# yin_bit.net
KiCad netlist of a schematic drawn in EAGLE
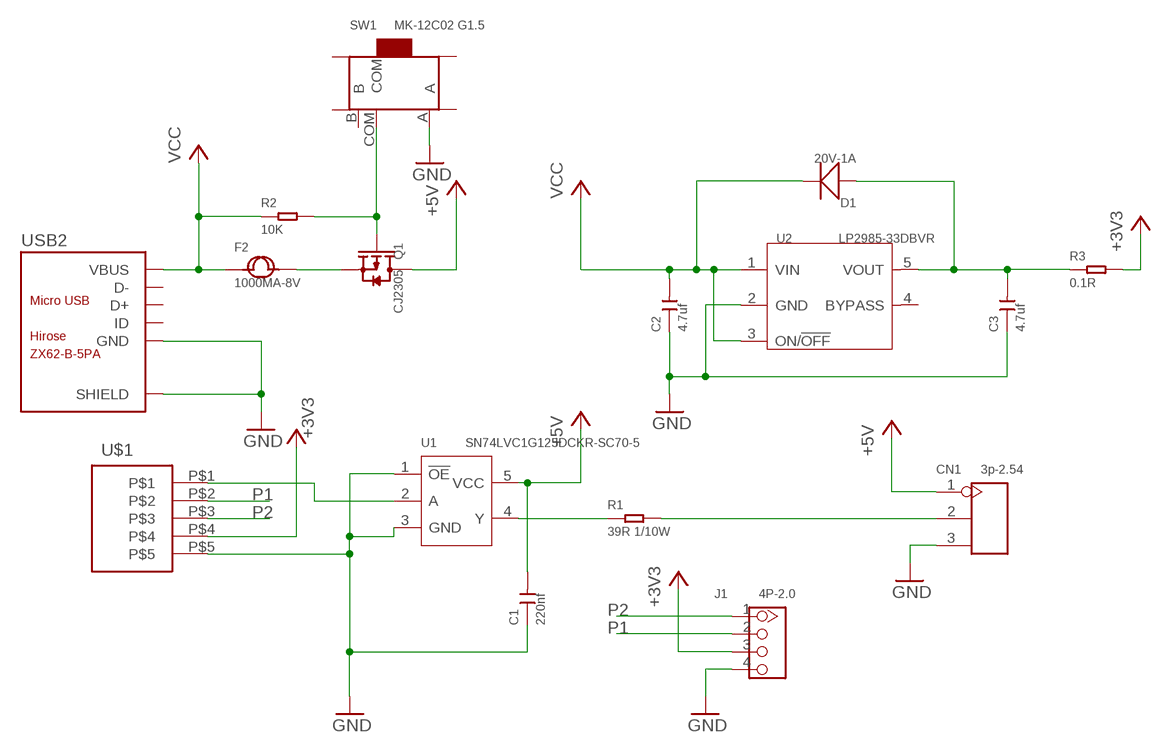
[diagram p0: schematic, sheet 1]

(export (version "E")
  (design (tool "Eeschema 10.0.6"))
  (components
    (comp (ref "C1")
      (value "220nf")
      (footprint "eagle-import:C0603")
      (fields (field (name "MPN") "CC0603KRX7R8BB224"))
      (libsource (lib "eagle-import") (part "CERAMIC-220NF-25V-10%-X7R(0603)"))
    )
    (comp (ref "C2")
      (value "4.7uf")
      (footprint "eagle-import:C0603")
      (fields (field (name "MPN") "CC0603KRX5R6BB475"))
      (libsource (lib "eagle-import") (part "CERAMIC-4.7UF-10V-10%-X5R(0603)"))
    )
    (comp (ref "C3")
      (value "4.7uf")
      (footprint "eagle-import:C0603")
      (fields (field (name "MPN") "CC0603KRX5R6BB475"))
      (libsource (lib "eagle-import") (part "CERAMIC-4.7UF-10V-10%-X5R(0603)"))
    )
    (comp (ref "CN1")
      (value "3p-2.54")
      (footprint "eagle-import:H3-2.54")
      (libsource (lib "eagle-import") (part "DIP-BLACK-MALE-HEADER-VERT(3P-2.54)"))
    )
    (comp (ref "D1")
      (value "20V-1A")
      (footprint "eagle-import:SOD-123")
      (fields (field (name "MPN") "B5819W"))
      (libsource (lib "eagle-import") (part "SMD-DIODE-SCHOTTKY-20V-1A(SOD-123)"))
    )
    (comp (ref "F2")
      (value "1000MA-8V")
      (footprint "eagle-import:F1206")
      (fields (field (name "MPN") "KT8-1000SMD1206"))
      (libsource (lib "eagle-import") (part "SMD-PPTC-1000MA-8V(1206)"))
    )
    (comp (ref "J1")
      (value "4P-2.0")
      (footprint "eagle-import:HW4-2.0")
      (libsource (lib "eagle-import") (part "GROVE-CONNECTOR-DIP(4P-2.0)"))
    )
    (comp (ref "Q1")
      (value "CJ2305")
      (footprint "eagle-import:SOT-23")
      (libsource (lib "eagle-import") (part "SMD-MOSFET-P-CH-8V-4.1A-CJ2305(SOT-23)"))
    )
    (comp (ref "R1")
      (value "39R 1/10W")
      (footprint "eagle-import:R0603")
      (fields (field (name "MPN") "RC0603JR-0739RL"))
      (libsource (lib "eagle-import") (part "SMD-RES-39R-5%-1/10W(0603)"))
    )
    (comp (ref "R2")
      (value "10K")
      (footprint "eagle-import:R0603")
      (fields (field (name "MPN") "RC0603FR-0710KL"))
      (libsource (lib "eagle-import") (part "SMD-RES-10K-1%-1/10W(0603)"))
    )
    (comp (ref "R3")
      (value "0.1R")
      (footprint "eagle-import:R0805")
      (fields (field (name "MPN") "RL0805JR-070R1L"))
      (libsource (lib "eagle-import") (part "SMD-RES-0.1R-5%-1/8W(0805)"))
    )
    (comp (ref "SW1")
      (value "MK-12C02 G1.5")
      (footprint "eagle-import:SW7-SMD-L6.7X2.7X3.2MM")
      (libsource (lib "eagle-import") (part "SMD-TOGGLE-SWITCH-ON-ON(3+4P-6.7X2.7MM)"))
    )
    (comp (ref "U$1")
      (value "MICROBIT-HOLL")
      (footprint "eagle-import:MICROBIT-HOLL")
      (libsource (lib "eagle-import") (part "MICROBIT-HOLL"))
    )
    (comp (ref "U1")
      (value "SN74LVC1G125DCKR-SC70-5")
      (footprint "eagle-import:SC-70-5")
      (fields (field (name "MPN") "SN74LVC1G125DCKR"))
      (libsource (lib "eagle-import") (part "LOGIC-SN74LVC1G125DCKR(SC70-5)"))
    )
    (comp (ref "U2")
      (value "LP2985-33DBVR")
      (footprint "eagle-import:SOT-23-5")
      (libsource (lib "eagle-import") (part "PMIC-LP2985-33DBVR(SOT23-5)"))
    )
    (comp (ref "USB2")
      (value "ZX62-B-5PA")
      (footprint "eagle-import:MICRO-USB5+6P-SMD-0.65-AB")
      (libsource (lib "eagle-import") (part "MICRO-USB-SMD(ZX62-B-5PA)"))
    )
  )
  (nets
    (net (code "1") (name "+3V3") (class "Default")
      (node (ref "J1") (pin "3") (pinfunction "3_3") (pintype "bidirectional"))
      (node (ref "R3") (pin "2") (pinfunction "2_2") (pintype "passive"))
      (node (ref "U$1") (pin "P$4") (pinfunction "P$4_P$4") (pintype "bidirectional"))
    )
    (net (code "2") (name "+5V") (class "Default")
      (node (ref "C1") (pin "2") (pinfunction "2_2") (pintype "passive"))
      (node (ref "CN1") (pin "1") (pinfunction "P$1_1") (pintype "bidirectional"))
      (node (ref "Q1") (pin "3") (pinfunction "D_3") (pintype "passive"))
      (node (ref "U1") (pin "5") (pinfunction "VCC_5") (pintype "bidirectional"))
    )
    (net (code "3") (name "/P1") (class "Default")
      (node (ref "J1") (pin "2") (pinfunction "2_2") (pintype "bidirectional"))
      (node (ref "U$1") (pin "P$2") (pinfunction "P$2_P$2") (pintype "bidirectional"))
    )
    (net (code "4") (name "/P2") (class "Default")
      (node (ref "J1") (pin "1") (pinfunction "1_1") (pintype "bidirectional"))
      (node (ref "U$1") (pin "P$3") (pinfunction "P$3_P$3") (pintype "bidirectional"))
    )
    (net (code "5") (name "GND") (class "Default")
      (node (ref "C1") (pin "1") (pinfunction "1_1") (pintype "passive"))
      (node (ref "C2") (pin "1") (pinfunction "1_1") (pintype "passive"))
      (node (ref "C3") (pin "1") (pinfunction "1_1") (pintype "passive"))
      (node (ref "CN1") (pin "3") (pinfunction "P$3_3") (pintype "bidirectional"))
      (node (ref "J1") (pin "4") (pinfunction "4_4") (pintype "bidirectional"))
      (node (ref "SW1") (pin "A") (pinfunction "A_A") (pintype "bidirectional"))
      (node (ref "U$1") (pin "P$5") (pinfunction "P$5_P$5") (pintype "bidirectional"))
      (node (ref "U1") (pin "1") (pinfunction "~{OE}_1") (pintype "bidirectional"))
      (node (ref "U1") (pin "3") (pinfunction "GND_3") (pintype "bidirectional"))
      (node (ref "U2") (pin "2") (pinfunction "GND_2") (pintype "bidirectional"))
      (node (ref "USB2") (pin "5") (pinfunction "GND_5") (pintype "power_in"))
      (node (ref "USB2") (pin "P1") (pinfunction "SHIELD_P1") (pintype "power_in"))
      (node (ref "USB2") (pin "P2") (pinfunction "SHIELD_P2") (pintype "power_in"))
      (node (ref "USB2") (pin "P3") (pinfunction "SHIELD_P3") (pintype "power_in"))
      (node (ref "USB2") (pin "P4") (pinfunction "SHIELD_P4") (pintype "power_in"))
      (node (ref "USB2") (pin "P5") (pinfunction "SHIELD_P5") (pintype "power_in"))
      (node (ref "USB2") (pin "P6") (pinfunction "SHIELD_P6") (pintype "power_in"))
    )
    (net (code "6") (name "Net-(CN1-P$2)") (class "Default")
      (node (ref "CN1") (pin "2") (pinfunction "P$2_2") (pintype "bidirectional"))
      (node (ref "R1") (pin "2") (pinfunction "2_2") (pintype "passive"))
    )
    (net (code "7") (name "Net-(Q1-G)") (class "Default")
      (node (ref "Q1") (pin "1") (pinfunction "G_1") (pintype "passive"))
      (node (ref "R2") (pin "2") (pinfunction "2_2") (pintype "passive"))
      (node (ref "SW1") (pin "COM") (pinfunction "COM_COM") (pintype "bidirectional"))
    )
    (net (code "8") (name "Net-(Q1-S)") (class "Default")
      (node (ref "F2") (pin "2") (pinfunction "2_2") (pintype "bidirectional"))
      (node (ref "Q1") (pin "2") (pinfunction "S_2") (pintype "passive"))
    )
    (net (code "9") (name "Net-(U1-A)") (class "Default")
      (node (ref "U$1") (pin "P$1") (pinfunction "P$1_P$1") (pintype "bidirectional"))
      (node (ref "U1") (pin "2") (pinfunction "A_2") (pintype "bidirectional"))
    )
    (net (code "10") (name "Net-(U1-Y)") (class "Default")
      (node (ref "R1") (pin "1") (pinfunction "1_1") (pintype "passive"))
      (node (ref "U1") (pin "4") (pinfunction "Y_4") (pintype "bidirectional"))
    )
    (net (code "11") (name "Net-(U2-VOUT)") (class "Default")
      (node (ref "C3") (pin "2") (pinfunction "2_2") (pintype "passive"))
      (node (ref "D1") (pin "+") (pinfunction "+_+") (pintype "passive"))
      (node (ref "R3") (pin "1") (pinfunction "1_1") (pintype "passive"))
      (node (ref "U2") (pin "5") (pinfunction "VOUT_5") (pintype "bidirectional"))
    )
    (net (code "12") (name "VCC") (class "Default")
      (node (ref "C2") (pin "2") (pinfunction "2_2") (pintype "passive"))
      (node (ref "D1") (pin "-") (pinfunction "-_-") (pintype "passive"))
      (node (ref "F2") (pin "1") (pinfunction "1_1") (pintype "bidirectional"))
      (node (ref "R2") (pin "1") (pinfunction "1_1") (pintype "passive"))
      (node (ref "U2") (pin "1") (pinfunction "VIN_1") (pintype "bidirectional"))
      (node (ref "U2") (pin "3") (pinfunction "ON/~{OFF}_3") (pintype "bidirectional"))
      (node (ref "USB2") (pin "1") (pinfunction "VBUS_1") (pintype "power_in"))
    )
    (net (code "13") (name "unconnected-(SW1-PadB)") (class "Default")
      (node (ref "SW1") (pin "B") (pinfunction "B_B") (pintype "bidirectional"))
    )
    (net (code "14") (name "unconnected-(SW1-PadSS1)") (class "Default")
      (node (ref "SW1") (pin "SS1") (pinfunction "SS1_SS1") (pintype "bidirectional"))
    )
    (net (code "15") (name "unconnected-(SW1-PadSS2)") (class "Default")
      (node (ref "SW1") (pin "SS2") (pinfunction "SS2_SS2") (pintype "bidirectional"))
    )
    (net (code "16") (name "unconnected-(SW1-PadSS3)") (class "Default")
      (node (ref "SW1") (pin "SS3") (pinfunction "SS3_SS3") (pintype "bidirectional"))
    )
    (net (code "17") (name "unconnected-(SW1-PadSS4)") (class "Default")
      (node (ref "SW1") (pin "SS4") (pinfunction "SS4_SS4") (pintype "bidirectional"))
    )
    (net (code "18") (name "unconnected-(U2-BYPASS-Pad4)") (class "Default")
      (node (ref "U2") (pin "4") (pinfunction "BYPASS_4") (pintype "bidirectional"))
    )
    (net (code "19") (name "unconnected-(USB2-D+-Pad3)") (class "Default")
      (node (ref "USB2") (pin "3") (pinfunction "D+_3") (pintype "bidirectional"))
    )
    (net (code "20") (name "unconnected-(USB2-D--Pad2)") (class "Default")
      (node (ref "USB2") (pin "2") (pinfunction "D-_2") (pintype "bidirectional"))
    )
    (net (code "21") (name "unconnected-(USB2-ID-Pad4)") (class "Default")
      (node (ref "USB2") (pin "4") (pinfunction "ID_4") (pintype "bidirectional"))
    )
  )
)
